# RPi0PWR.net
KiCad netlist of a schematic drawn in EAGLE
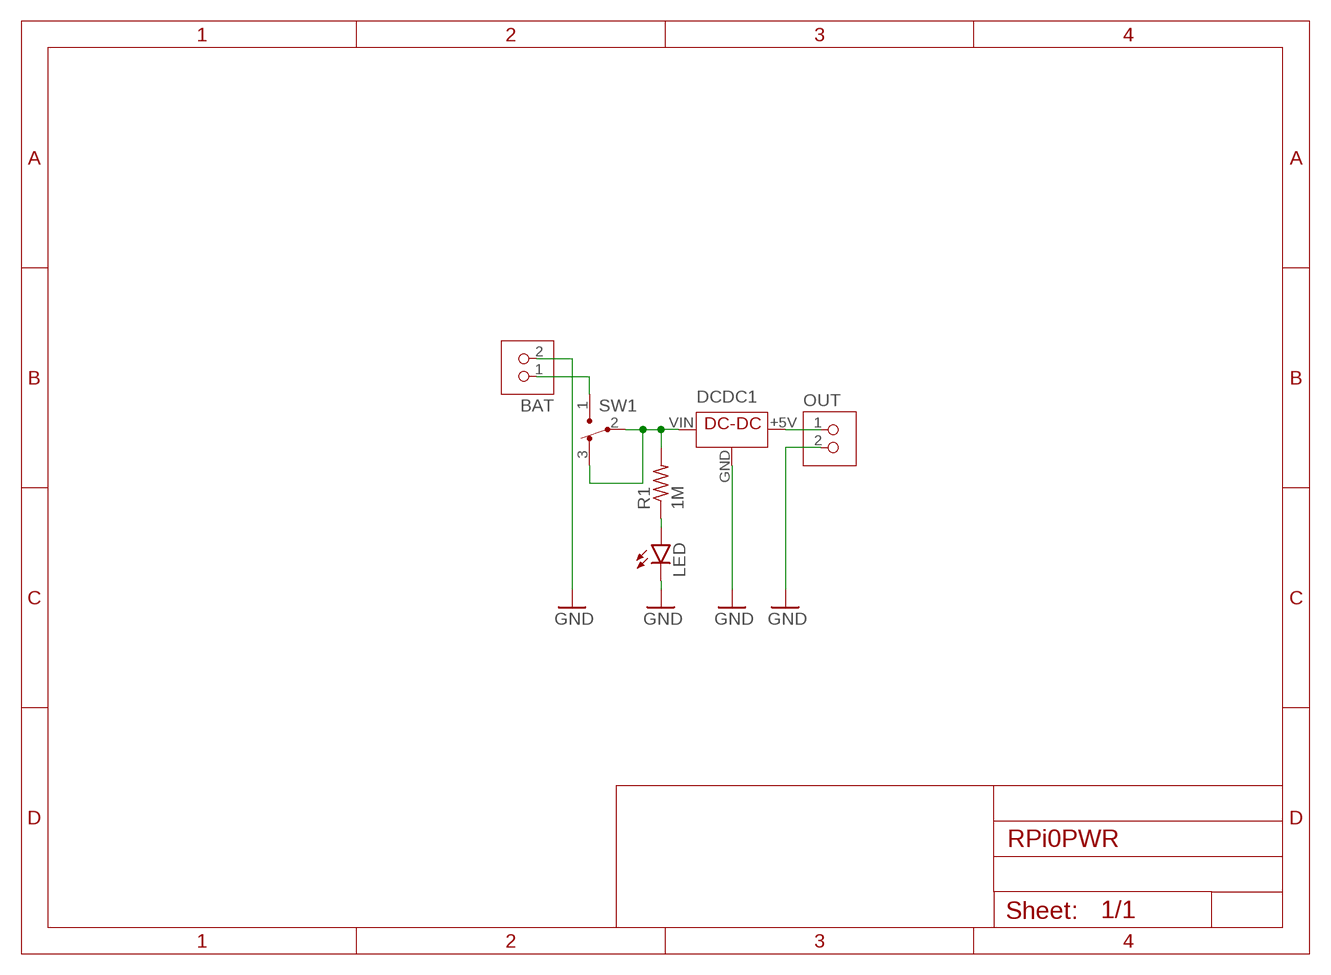
[diagram p0: schematic, sheet 1]

(export (version "E")
  (design (tool "Eeschema 10.0.6"))
  (components
    (comp (ref "BAT")
      (value "JST-PH2")
      (footprint "eagle-import:JST-PH2")
      (libsource (lib "eagle-import") (part "JST-PH2"))
    )
    (comp (ref "DCDC1")
      (value "DCDC-5V-0.48A")
      (footprint "eagle-import:DCDC-5V-0.48A")
      (libsource (lib "eagle-import") (part "DCDC-5V-0.48A"))
    )
    (comp (ref "LED")
      (value "LED3MM")
      (footprint "eagle-import:LED3MM")
      (libsource (lib "eagle-import") (part "LED3MM"))
    )
    (comp (ref "OUT")
      (value "JST-PH2")
      (footprint "eagle-import:JST-PH2")
      (libsource (lib "eagle-import") (part "JST-PH2"))
    )
    (comp (ref "R1")
      (value "1M")
      (footprint "eagle-import:0204_5")
      (libsource (lib "eagle-import") (part "R-US_0204/5"))
    )
    (comp (ref "SW1")
      (value "SW3-1")
      (footprint "eagle-import:SW3-1")
      (fields (field (name "MF") "HiLetgo"))
      (libsource (lib "eagle-import") (part "SW3-1"))
    )
  )
  (nets
    (net (code "1") (name "GND") (class "Default")
      (node (ref "BAT") (pin "2") (pinfunction "2_2") (pintype "passive"))
      (node (ref "DCDC1") (pin "GND") (pinfunction "GND_GND") (pintype "power_in"))
      (node (ref "LED") (pin "K") (pinfunction "C_K") (pintype "passive"))
      (node (ref "OUT") (pin "2") (pinfunction "2_2") (pintype "passive"))
    )
    (net (code "2") (name "Net-(BAT-Pad1)") (class "Default")
      (node (ref "BAT") (pin "1") (pinfunction "1_1") (pintype "passive"))
      (node (ref "SW1") (pin "1") (pinfunction "1_1") (pintype "passive"))
    )
    (net (code "3") (name "Net-(DCDC1-PadVIN)") (class "Default")
      (node (ref "DCDC1") (pin "VIN") (pinfunction "VIN_VIN") (pintype "power_in"))
      (node (ref "R1") (pin "2") (pinfunction "2_2") (pintype "passive"))
      (node (ref "SW1") (pin "2") (pinfunction "2_2") (pintype "passive"))
      (node (ref "SW1") (pin "3") (pinfunction "3_3") (pintype "passive"))
    )
    (net (code "4") (name "Net-(DCDC1-VOUT)") (class "Default")
      (node (ref "DCDC1") (pin "+5V") (pinfunction "VOUT_+5V") (pintype "power_in"))
      (node (ref "OUT") (pin "1") (pinfunction "1_1") (pintype "passive"))
    )
    (net (code "5") (name "Net-(LED-PadA)") (class "Default")
      (node (ref "LED") (pin "A") (pinfunction "A_A") (pintype "passive"))
      (node (ref "R1") (pin "1") (pinfunction "1_1") (pintype "passive"))
    )
  )
)
